# IR_SENSOR.net
KiCad netlist of a schematic drawn in EAGLE
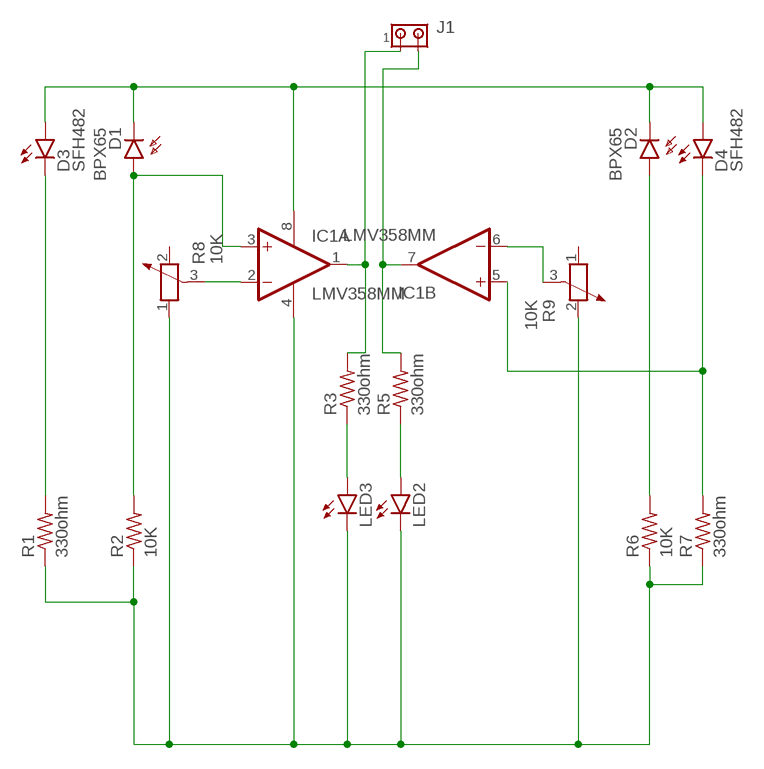
[diagram p0: schematic, sheet 1]

(export (version "E")
  (design (tool "Eeschema 10.0.6"))
  (components
    (comp (ref "D1")
      (value "BPX65")
      (footprint "eagle-import:BPX65")
      (fields (field (name "MPN") "BPX65."))
      (libsource (lib "eagle-import") (part "BPX65"))
    )
    (comp (ref "D2")
      (value "BPX65")
      (footprint "eagle-import:BPX65")
      (fields (field (name "MPN") "BPX65."))
      (libsource (lib "eagle-import") (part "BPX65"))
    )
    (comp (ref "D3")
      (value "SFH482")
      (footprint "eagle-import:SFH482")
      (libsource (lib "eagle-import") (part "SFH482"))
    )
    (comp (ref "D4")
      (value "SFH482")
      (footprint "eagle-import:SFH482")
      (libsource (lib "eagle-import") (part "SFH482"))
    )
    (comp (ref "IC1")
      (value "LMV358MM")
      (footprint "eagle-import:MSOP08")
      (libsource (lib "eagle-import") (part "LMV358?MM"))
    )
    (comp (ref "J1")
      (value "MTA02-100")
      (footprint "eagle-import:10X02MTA")
      (libsource (lib "eagle-import") (part "MTA02-100"))
    )
    (comp (ref "LED2")
      (value "LED3MM")
      (footprint "eagle-import:LED3MM")
      (libsource (lib "eagle-import") (part "LED3MM"))
    )
    (comp (ref "LED3")
      (value "LED3MM")
      (footprint "eagle-import:LED3MM")
      (libsource (lib "eagle-import") (part "LED3MM"))
    )
    (comp (ref "R1")
      (value "330ohm")
      (footprint "eagle-import:0207_10")
      (libsource (lib "eagle-import") (part "R-US_0207/10"))
    )
    (comp (ref "R2")
      (value "10K")
      (footprint "eagle-import:0207_10")
      (libsource (lib "eagle-import") (part "R-US_0207/10"))
    )
    (comp (ref "R3")
      (value "330ohm")
      (footprint "eagle-import:0207_10")
      (libsource (lib "eagle-import") (part "R-US_0207/10"))
    )
    (comp (ref "R5")
      (value "330ohm")
      (footprint "eagle-import:0207_10")
      (libsource (lib "eagle-import") (part "R-US_0207/10"))
    )
    (comp (ref "R6")
      (value "10K")
      (footprint "eagle-import:0207_10")
      (libsource (lib "eagle-import") (part "R-US_0207/10"))
    )
    (comp (ref "R7")
      (value "330ohm")
      (footprint "eagle-import:0207_10")
      (libsource (lib "eagle-import") (part "R-US_0207/10"))
    )
    (comp (ref "R8")
      (value "10K")
      (footprint "eagle-import:PT-10")
      (libsource (lib "eagle-import") (part "POTENTIOMETER_PT-10"))
    )
    (comp (ref "R9")
      (value "10K")
      (footprint "eagle-import:PT-10")
      (libsource (lib "eagle-import") (part "POTENTIOMETER_PT-10"))
    )
  )
  (nets
    (net (code "1") (name "Net-(D1-C)") (class "Default")
      (node (ref "D1") (pin "K") (pinfunction "C_K") (pintype "passive"))
      (node (ref "D2") (pin "K") (pinfunction "C_K") (pintype "passive"))
      (node (ref "D3") (pin "A") (pinfunction "A_A") (pintype "passive"))
      (node (ref "D4") (pin "A") (pinfunction "A_A") (pintype "passive"))
      (node (ref "IC1") (pin "8") (pinfunction "V+_8") (pintype "power_in"))
    )
    (net (code "2") (name "Net-(D2-PadA)") (class "Default")
      (node (ref "D2") (pin "A") (pinfunction "A_A") (pintype "passive"))
      (node (ref "R6") (pin "2") (pinfunction "2_2") (pintype "passive"))
    )
    (net (code "3") (name "Net-(D3-C)") (class "Default")
      (node (ref "D3") (pin "K") (pinfunction "C_K") (pintype "passive"))
      (node (ref "R1") (pin "2") (pinfunction "2_2") (pintype "passive"))
    )
    (net (code "4") (name "Net-(D4-C)") (class "Default")
      (node (ref "D4") (pin "K") (pinfunction "C_K") (pintype "passive"))
      (node (ref "IC1") (pin "5") (pinfunction "+IN_5") (pintype "input"))
      (node (ref "R7") (pin "2") (pinfunction "2_2") (pintype "passive"))
    )
    (net (code "5") (name "Net-(IC1A-+IN)") (class "Default")
      (node (ref "D1") (pin "A") (pinfunction "A_A") (pintype "passive"))
      (node (ref "IC1") (pin "3") (pinfunction "+IN_3") (pintype "input"))
      (node (ref "R2") (pin "2") (pinfunction "2_2") (pintype "passive"))
    )
    (net (code "6") (name "Net-(IC1A--IN)") (class "Default")
      (node (ref "IC1") (pin "2") (pinfunction "-IN_2") (pintype "input"))
      (node (ref "R8") (pin "3") (pinfunction "3_3") (pintype "passive"))
    )
    (net (code "7") (name "Net-(IC1A-OUT)") (class "Default")
      (node (ref "IC1") (pin "1") (pinfunction "OUT_1") (pintype "output"))
      (node (ref "J1") (pin "1") (pinfunction "1_1") (pintype "passive"))
      (node (ref "R3") (pin "2") (pinfunction "2_2") (pintype "passive"))
    )
    (net (code "8") (name "Net-(IC1B--IN)") (class "Default")
      (node (ref "IC1") (pin "6") (pinfunction "-IN_6") (pintype "input"))
      (node (ref "R9") (pin "3") (pinfunction "3_3") (pintype "passive"))
    )
    (net (code "9") (name "Net-(IC1B-OUT)") (class "Default")
      (node (ref "IC1") (pin "7") (pinfunction "OUT_7") (pintype "output"))
      (node (ref "J1") (pin "2") (pinfunction "2_2") (pintype "passive"))
      (node (ref "R5") (pin "2") (pinfunction "2_2") (pintype "passive"))
    )
    (net (code "10") (name "Net-(IC1C-V-)") (class "Default")
      (node (ref "IC1") (pin "4") (pinfunction "V-_4") (pintype "power_in"))
      (node (ref "LED2") (pin "K") (pinfunction "C_K") (pintype "passive"))
      (node (ref "LED3") (pin "K") (pinfunction "C_K") (pintype "passive"))
      (node (ref "R1") (pin "1") (pinfunction "1_1") (pintype "passive"))
      (node (ref "R2") (pin "1") (pinfunction "1_1") (pintype "passive"))
      (node (ref "R6") (pin "1") (pinfunction "1_1") (pintype "passive"))
      (node (ref "R7") (pin "1") (pinfunction "1_1") (pintype "passive"))
      (node (ref "R8") (pin "1") (pinfunction "1_1") (pintype "passive"))
      (node (ref "R9") (pin "2") (pinfunction "2_2") (pintype "passive"))
    )
    (net (code "11") (name "Net-(LED2-PadA)") (class "Default")
      (node (ref "LED2") (pin "A") (pinfunction "A_A") (pintype "passive"))
      (node (ref "R5") (pin "1") (pinfunction "1_1") (pintype "passive"))
    )
    (net (code "12") (name "Net-(LED3-PadA)") (class "Default")
      (node (ref "LED3") (pin "A") (pinfunction "A_A") (pintype "passive"))
      (node (ref "R3") (pin "1") (pinfunction "1_1") (pintype "passive"))
    )
    (net (code "13") (name "unconnected-(R8-Pad2)") (class "Default")
      (node (ref "R8") (pin "2") (pinfunction "2_2") (pintype "passive"))
    )
    (net (code "14") (name "unconnected-(R9-Pad1)") (class "Default")
      (node (ref "R9") (pin "1") (pinfunction "1_1") (pintype "passive"))
    )
  )
)
